# Schemat.net
KiCad netlist of a schematic drawn in EAGLE
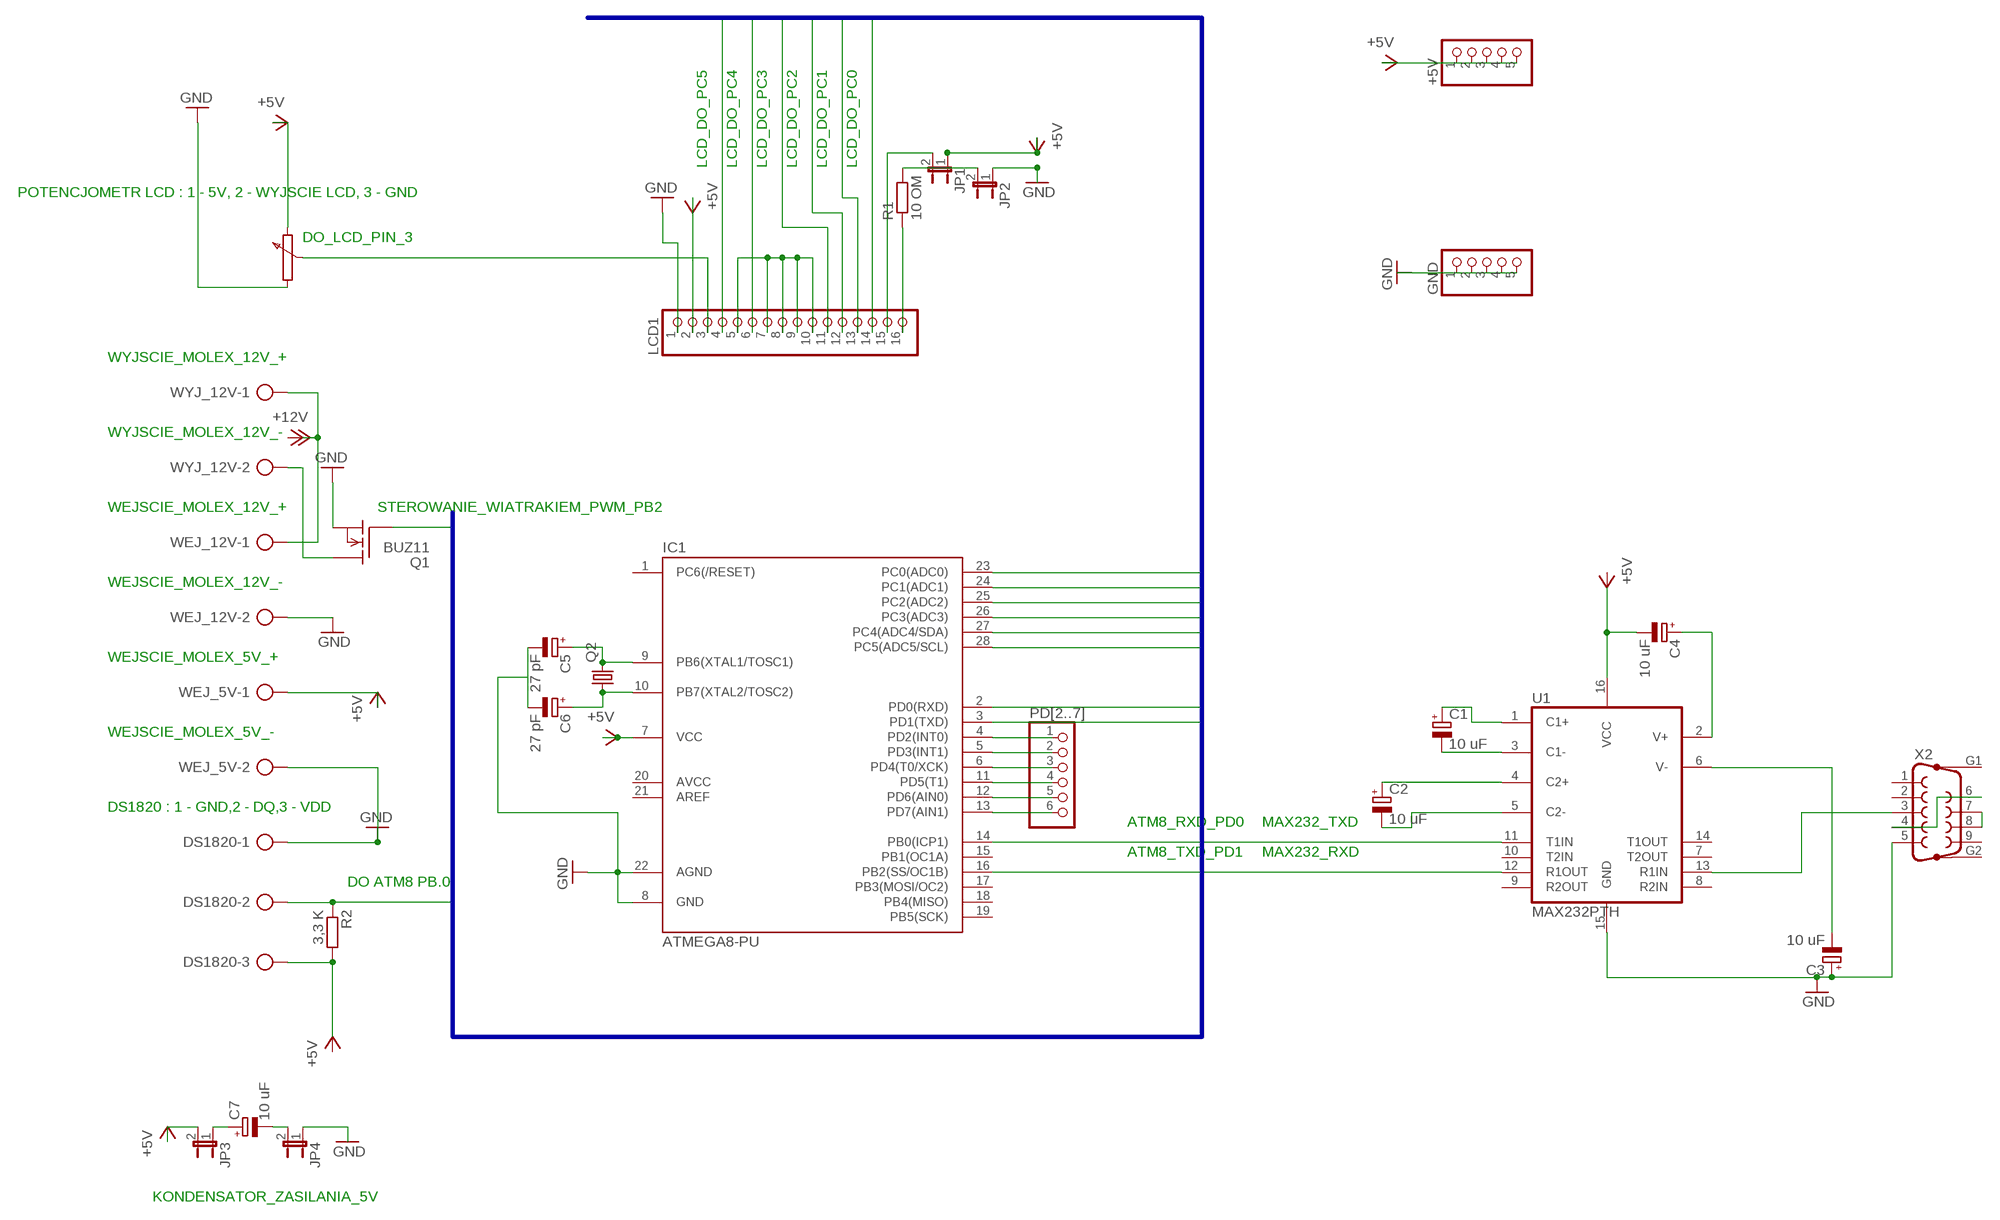
[diagram p0: schematic, sheet 1]

(export (version "E")
  (design (tool "Eeschema 10.0.6"))
  (components
    (comp (ref "+5V")
      (value "PINHD-1X5")
      (footprint "eagle-import:1X05")
      (libsource (lib "eagle-import") (part "PINHD-1X5"))
    )
    (comp (ref "C1")
      (value "10 uF")
      (footprint "eagle-import:E5-10,5")
      (libsource (lib "eagle-import") (part "CPOL-EUE5-10.5"))
    )
    (comp (ref "C2")
      (value "10 uF")
      (footprint "eagle-import:E5-10,5")
      (libsource (lib "eagle-import") (part "CPOL-EUE5-10.5"))
    )
    (comp (ref "C3")
      (value "10 uF")
      (footprint "eagle-import:E5-10,5")
      (libsource (lib "eagle-import") (part "CPOL-EUE5-10.5"))
    )
    (comp (ref "C4")
      (value "10 uF")
      (footprint "eagle-import:E5-10,5")
      (libsource (lib "eagle-import") (part "CPOL-EUE5-10.5"))
    )
    (comp (ref "C5")
      (value "27 pF")
      (footprint "eagle-import:E5-10,5")
      (libsource (lib "eagle-import") (part "CPOL-EUE5-10.5"))
    )
    (comp (ref "C6")
      (value "27 pF")
      (footprint "eagle-import:E5-10,5")
      (libsource (lib "eagle-import") (part "CPOL-EUE5-10.5"))
    )
    (comp (ref "C7")
      (value "10 uF")
      (footprint "eagle-import:E5-10,5")
      (libsource (lib "eagle-import") (part "CPOL-EUE5-10.5"))
    )
    (comp (ref "DS1820")
      (value "AK500/3-H")
      (footprint "eagle-import:AK500_3-H")
      (libsource (lib "eagle-import") (part "AK500/3-H"))
    )
    (comp (ref "GND")
      (value "PINHD-1X5")
      (footprint "eagle-import:1X05")
      (libsource (lib "eagle-import") (part "PINHD-1X5"))
    )
    (comp (ref "IC1")
      (value "ATMEGA8-PU")
      (footprint "eagle-import:DIL28-3")
      (libsource (lib "eagle-import") (part "ATMEGA8-PU"))
    )
    (comp (ref "JP1")
      (value "JP1E")
      (footprint "eagle-import:JP1")
      (libsource (lib "eagle-import") (part "JP1E"))
    )
    (comp (ref "JP2")
      (value "JP1E")
      (footprint "eagle-import:JP1")
      (libsource (lib "eagle-import") (part "JP1E"))
    )
    (comp (ref "JP3")
      (value "JP1E")
      (footprint "eagle-import:JP1")
      (libsource (lib "eagle-import") (part "JP1E"))
    )
    (comp (ref "JP4")
      (value "JP1E")
      (footprint "eagle-import:JP1")
      (libsource (lib "eagle-import") (part "JP1E"))
    )
    (comp (ref "LCD1")
      (value "PINHD-1X16")
      (footprint "eagle-import:1X16")
      (libsource (lib "eagle-import") (part "PINHD-1X16"))
    )
    (comp (ref "PD[2..7]")
      (value "PINHD-1X6")
      (footprint "eagle-import:1X06")
      (libsource (lib "eagle-import") (part "PINHD-1X6"))
    )
    (comp (ref "Q1")
      (value "BUZ11")
      (footprint "eagle-import:TO220")
      (libsource (lib "eagle-import") (part "BUZ11"))
    )
    (comp (ref "Q2")
      (value "CRYSTALHC49S")
      (footprint "eagle-import:HC49_S")
      (libsource (lib "eagle-import") (part "CRYSTALHC49S"))
    )
    (comp (ref "R1")
      (value "10 OM")
      (footprint "eagle-import:0207_15")
      (libsource (lib "eagle-import") (part "R-EU_0207/15"))
    )
    (comp (ref "R2")
      (value "3,3 K")
      (footprint "eagle-import:0207_15")
      (libsource (lib "eagle-import") (part "R-EU_0207/15"))
    )
    (comp (ref "U1")
      (value "MAX232PTH")
      (footprint "eagle-import:DIL16")
      (libsource (lib "eagle-import") (part "MAX232PTH"))
    )
    (comp (ref "WEJ_5V")
      (value "AK500/2-H")
      (footprint "eagle-import:AK500_2-H")
      (libsource (lib "eagle-import") (part "AK500/2-H"))
    )
    (comp (ref "WEJ_12V")
      (value "AK500/2-H")
      (footprint "eagle-import:AK500_2-H")
      (libsource (lib "eagle-import") (part "AK500/2-H"))
    )
    (comp (ref "WYJ_12V")
      (value "AK500/2-H")
      (footprint "eagle-import:AK500_2-H")
      (libsource (lib "eagle-import") (part "AK500/2-H"))
    )
    (comp (ref "X2")
      (value "F09HP")
      (footprint "eagle-import:F09HP")
      (libsource (lib "eagle-import") (part "F09HP"))
    )
  )
  (nets
    (net (code "1") (name "+5V") (class "Default")
      (node (ref "+5V") (pin "1") (pinfunction "1_1") (pintype "passive"))
      (node (ref "+5V") (pin "2") (pinfunction "2_2") (pintype "passive"))
      (node (ref "+5V") (pin "3") (pinfunction "3_3") (pintype "passive"))
      (node (ref "+5V") (pin "4") (pinfunction "4_4") (pintype "passive"))
      (node (ref "+5V") (pin "5") (pinfunction "5_5") (pintype "passive"))
      (node (ref "IC1") (pin "7") (pinfunction "VCC_7") (pintype "power_in"))
      (node (ref "JP1") (pin "1") (pinfunction "1_1") (pintype "passive"))
      (node (ref "JP3") (pin "2") (pinfunction "2_2") (pintype "passive"))
      (node (ref "LCD1") (pin "2") (pinfunction "2_2") (pintype "passive"))
      (node (ref "WEJ_5V") (pin "1") (pinfunction "KL_1") (pintype "passive"))
    )
    (net (code "3") (name "/PB0") (class "Default")
      (node (ref "DS1820") (pin "2") (pinfunction "KL_2") (pintype "passive"))
      (node (ref "IC1") (pin "14") (pinfunction "PB0(ICP1)_14") (pintype "bidirectional"))
      (node (ref "R2") (pin "1") (pinfunction "1_1") (pintype "passive"))
    )
    (net (code "4") (name "/PB2") (class "Default")
      (node (ref "IC1") (pin "16") (pinfunction "PB2(SS/OC1B)_16") (pintype "bidirectional"))
      (node (ref "Q1") (pin "1") (pinfunction "G_1") (pintype "passive"))
    )
    (net (code "5") (name "/PC0") (class "Default")
      (node (ref "IC1") (pin "23") (pinfunction "PC0(ADC0)_23") (pintype "bidirectional"))
      (node (ref "LCD1") (pin "14") (pinfunction "14_14") (pintype "passive"))
    )
    (net (code "6") (name "/PC1") (class "Default")
      (node (ref "IC1") (pin "24") (pinfunction "PC1(ADC1)_24") (pintype "bidirectional"))
      (node (ref "LCD1") (pin "13") (pinfunction "13_13") (pintype "passive"))
    )
    (net (code "7") (name "/PC2") (class "Default")
      (node (ref "IC1") (pin "25") (pinfunction "PC2(ADC2)_25") (pintype "bidirectional"))
      (node (ref "LCD1") (pin "12") (pinfunction "12_12") (pintype "passive"))
    )
    (net (code "8") (name "/PC3") (class "Default")
      (node (ref "IC1") (pin "26") (pinfunction "PC3(ADC3)_26") (pintype "bidirectional"))
      (node (ref "LCD1") (pin "11") (pinfunction "11_11") (pintype "passive"))
    )
    (net (code "9") (name "/PC4") (class "Default")
      (node (ref "IC1") (pin "27") (pinfunction "PC4(ADC4/SDA)_27") (pintype "bidirectional"))
      (node (ref "LCD1") (pin "6") (pinfunction "6_6") (pintype "passive"))
    )
    (net (code "10") (name "/PC5") (class "Default")
      (node (ref "IC1") (pin "28") (pinfunction "PC5(ADC5/SCL)_28") (pintype "bidirectional"))
      (node (ref "LCD1") (pin "4") (pinfunction "4_4") (pintype "passive"))
    )
    (net (code "11") (name "/PD0") (class "Default")
      (node (ref "IC1") (pin "2") (pinfunction "PD0(RXD)_2") (pintype "bidirectional"))
      (node (ref "U1") (pin "11") (pinfunction "T1IN_11") (pintype "input"))
    )
    (net (code "12") (name "/PD1") (class "Default")
      (node (ref "IC1") (pin "3") (pinfunction "PD1(TXD)_3") (pintype "bidirectional"))
      (node (ref "U1") (pin "12") (pinfunction "R1OUT_12") (pintype "output"))
    )
    (net (code "13") (name "GND") (class "Default")
      (node (ref "C3") (pin "+") (pinfunction "+_+") (pintype "passive"))
      (node (ref "C5") (pin "-") (pinfunction "-_-") (pintype "passive"))
      (node (ref "C6") (pin "-") (pinfunction "-_-") (pintype "passive"))
      (node (ref "DS1820") (pin "1") (pinfunction "KL_1") (pintype "passive"))
      (node (ref "GND") (pin "1") (pinfunction "1_1") (pintype "passive"))
      (node (ref "GND") (pin "2") (pinfunction "2_2") (pintype "passive"))
      (node (ref "GND") (pin "3") (pinfunction "3_3") (pintype "passive"))
      (node (ref "GND") (pin "4") (pinfunction "4_4") (pintype "passive"))
      (node (ref "GND") (pin "5") (pinfunction "5_5") (pintype "passive"))
      (node (ref "IC1") (pin "22") (pinfunction "AGND_22") (pintype "power_in"))
      (node (ref "IC1") (pin "8") (pinfunction "GND_8") (pintype "power_in"))
      (node (ref "JP2") (pin "1") (pinfunction "1_1") (pintype "passive"))
      (node (ref "JP4") (pin "1") (pinfunction "1_1") (pintype "passive"))
      (node (ref "LCD1") (pin "1") (pinfunction "1_1") (pintype "passive"))
      (node (ref "Q1") (pin "3") (pinfunction "S_3") (pintype "passive"))
      (node (ref "U1") (pin "15") (pinfunction "GND_15") (pintype "bidirectional"))
      (node (ref "WEJ_12V") (pin "2") (pinfunction "KL_2") (pintype "passive"))
      (node (ref "WEJ_5V") (pin "2") (pinfunction "KL_2") (pintype "passive"))
      (node (ref "X2") (pin "5") (pinfunction "5_5") (pintype "passive"))
    )
    (net (code "14") (name "Net-(C7-Pad+)") (class "Default")
      (node (ref "C7") (pin "+") (pinfunction "+_+") (pintype "passive"))
      (node (ref "JP3") (pin "1") (pinfunction "1_1") (pintype "passive"))
    )
    (net (code "15") (name "Net-(C7-Pad-)") (class "Default")
      (node (ref "C7") (pin "-") (pinfunction "-_-") (pintype "passive"))
      (node (ref "JP4") (pin "2") (pinfunction "2_2") (pintype "passive"))
    )
    (net (code "16") (name "Net-(DS1820C-KL)") (class "Default")
      (node (ref "DS1820") (pin "3") (pinfunction "KL_3") (pintype "passive"))
      (node (ref "R2") (pin "2") (pinfunction "2_2") (pintype "passive"))
    )
    (net (code "17") (name "Net-(IC1-PB6(XTAL1{slash}TOSC1))") (class "Default")
      (node (ref "C5") (pin "+") (pinfunction "+_+") (pintype "passive"))
      (node (ref "IC1") (pin "9") (pinfunction "PB6(XTAL1/TOSC1)_9") (pintype "bidirectional"))
      (node (ref "Q2") (pin "2") (pinfunction "2_2") (pintype "passive"))
    )
    (net (code "18") (name "Net-(IC1-PB7(XTAL2{slash}TOSC2))") (class "Default")
      (node (ref "C6") (pin "+") (pinfunction "+_+") (pintype "passive"))
      (node (ref "IC1") (pin "10") (pinfunction "PB7(XTAL2/TOSC2)_10") (pintype "bidirectional"))
      (node (ref "Q2") (pin "1") (pinfunction "1_1") (pintype "passive"))
    )
    (net (code "19") (name "Net-(IC1-PD2(INT0))") (class "Default")
      (node (ref "IC1") (pin "4") (pinfunction "PD2(INT0)_4") (pintype "bidirectional"))
      (node (ref "PD[2..7]") (pin "1") (pinfunction "1_1") (pintype "passive"))
    )
    (net (code "20") (name "Net-(IC1-PD3(INT1))") (class "Default")
      (node (ref "IC1") (pin "5") (pinfunction "PD3(INT1)_5") (pintype "bidirectional"))
      (node (ref "PD[2..7]") (pin "2") (pinfunction "2_2") (pintype "passive"))
    )
    (net (code "21") (name "Net-(IC1-PD4(T0{slash}XCK))") (class "Default")
      (node (ref "IC1") (pin "6") (pinfunction "PD4(T0/XCK)_6") (pintype "bidirectional"))
      (node (ref "PD[2..7]") (pin "3") (pinfunction "3_3") (pintype "passive"))
    )
    (net (code "22") (name "Net-(IC1-PD5(T1))") (class "Default")
      (node (ref "IC1") (pin "11") (pinfunction "PD5(T1)_11") (pintype "bidirectional"))
      (node (ref "PD[2..7]") (pin "4") (pinfunction "4_4") (pintype "passive"))
    )
    (net (code "23") (name "Net-(IC1-PD6(AIN0))") (class "Default")
      (node (ref "IC1") (pin "12") (pinfunction "PD6(AIN0)_12") (pintype "bidirectional"))
      (node (ref "PD[2..7]") (pin "5") (pinfunction "5_5") (pintype "passive"))
    )
    (net (code "24") (name "Net-(IC1-PD7(AIN1))") (class "Default")
      (node (ref "IC1") (pin "13") (pinfunction "PD7(AIN1)_13") (pintype "bidirectional"))
      (node (ref "PD[2..7]") (pin "6") (pinfunction "6_6") (pintype "passive"))
    )
    (net (code "25") (name "Net-(JP1-Pad2)") (class "Default")
      (node (ref "JP1") (pin "2") (pinfunction "2_2") (pintype "passive"))
      (node (ref "LCD1") (pin "15") (pinfunction "15_15") (pintype "passive"))
    )
    (net (code "26") (name "Net-(JP2-Pad2)") (class "Default")
      (node (ref "JP2") (pin "2") (pinfunction "2_2") (pintype "passive"))
      (node (ref "R1") (pin "2") (pinfunction "2_2") (pintype "passive"))
    )
    (net (code "27") (name "Net-(LCD1-Pad10)") (class "Default")
      (node (ref "LCD1") (pin "10") (pinfunction "10_10") (pintype "passive"))
      (node (ref "LCD1") (pin "5") (pinfunction "5_5") (pintype "passive"))
      (node (ref "LCD1") (pin "7") (pinfunction "7_7") (pintype "passive"))
      (node (ref "LCD1") (pin "8") (pinfunction "8_8") (pintype "passive"))
      (node (ref "LCD1") (pin "9") (pinfunction "9_9") (pintype "passive"))
    )
    (net (code "28") (name "Net-(LCD1-Pad16)") (class "Default")
      (node (ref "LCD1") (pin "16") (pinfunction "16_16") (pintype "passive"))
      (node (ref "R1") (pin "1") (pinfunction "1_1") (pintype "passive"))
    )
    (net (code "29") (name "Net-(Q1-D)") (class "Default")
      (node (ref "Q1") (pin "2") (pinfunction "D_2") (pintype "passive"))
      (node (ref "WYJ_12V") (pin "2") (pinfunction "KL_2") (pintype "passive"))
    )
    (net (code "30") (name "Net-(U1-C1+)") (class "Default")
      (node (ref "C1") (pin "+") (pinfunction "+_+") (pintype "passive"))
      (node (ref "U1") (pin "1") (pinfunction "C1+_1") (pintype "bidirectional"))
    )
    (net (code "31") (name "Net-(U1-C1-)") (class "Default")
      (node (ref "C1") (pin "-") (pinfunction "-_-") (pintype "passive"))
      (node (ref "U1") (pin "3") (pinfunction "C1-_3") (pintype "bidirectional"))
    )
    (net (code "32") (name "Net-(U1-C2+)") (class "Default")
      (node (ref "C2") (pin "+") (pinfunction "+_+") (pintype "passive"))
      (node (ref "U1") (pin "4") (pinfunction "C2+_4") (pintype "bidirectional"))
    )
    (net (code "33") (name "Net-(U1-C2-)") (class "Default")
      (node (ref "C2") (pin "-") (pinfunction "-_-") (pintype "passive"))
      (node (ref "U1") (pin "5") (pinfunction "C2-_5") (pintype "bidirectional"))
    )
    (net (code "34") (name "Net-(U1-R1IN)") (class "Default")
      (node (ref "U1") (pin "13") (pinfunction "R1IN_13") (pintype "input"))
      (node (ref "X2") (pin "3") (pinfunction "3_3") (pintype "passive"))
    )
    (net (code "35") (name "Net-(U1-V+)") (class "Default")
      (node (ref "C4") (pin "+") (pinfunction "+_+") (pintype "passive"))
      (node (ref "U1") (pin "2") (pinfunction "V+_2") (pintype "bidirectional"))
    )
    (net (code "36") (name "Net-(U1-V-)") (class "Default")
      (node (ref "C3") (pin "-") (pinfunction "-_-") (pintype "passive"))
      (node (ref "U1") (pin "6") (pinfunction "V-_6") (pintype "bidirectional"))
    )
    (net (code "37") (name "Net-(U1-VCC)") (class "Default")
      (node (ref "C4") (pin "-") (pinfunction "-_-") (pintype "passive"))
      (node (ref "U1") (pin "16") (pinfunction "VCC_16") (pintype "bidirectional"))
    )
    (net (code "38") (name "Net-(WEJ_12VA-KL)") (class "Default")
      (node (ref "WEJ_12V") (pin "1") (pinfunction "KL_1") (pintype "passive"))
      (node (ref "WYJ_12V") (pin "1") (pinfunction "KL_1") (pintype "passive"))
    )
    (net (code "39") (name "Net-(X2-Pad4)") (class "Default")
      (node (ref "X2") (pin "4") (pinfunction "4_4") (pintype "passive"))
      (node (ref "X2") (pin "6") (pinfunction "6_6") (pintype "passive"))
    )
    (net (code "40") (name "Net-(X2-Pad7)") (class "Default")
      (node (ref "X2") (pin "7") (pinfunction "7_7") (pintype "passive"))
      (node (ref "X2") (pin "8") (pinfunction "8_8") (pintype "passive"))
    )
    (net (code "41") (name "unconnected-(IC1-AREF-Pad21)") (class "Default")
      (node (ref "IC1") (pin "21") (pinfunction "AREF_21") (pintype "passive"))
    )
    (net (code "42") (name "unconnected-(IC1-AVCC-Pad20)") (class "Default")
      (node (ref "IC1") (pin "20") (pinfunction "AVCC_20") (pintype "passive"))
    )
    (net (code "43") (name "unconnected-(IC1-PB1(OC1A)-Pad15)") (class "Default")
      (node (ref "IC1") (pin "15") (pinfunction "PB1(OC1A)_15") (pintype "bidirectional"))
    )
    (net (code "44") (name "unconnected-(IC1-PB3(MOSI{slash}OC2)-Pad17)") (class "Default")
      (node (ref "IC1") (pin "17") (pinfunction "PB3(MOSI/OC2)_17") (pintype "bidirectional"))
    )
    (net (code "45") (name "unconnected-(IC1-PB4(MISO)-Pad18)") (class "Default")
      (node (ref "IC1") (pin "18") (pinfunction "PB4(MISO)_18") (pintype "bidirectional"))
    )
    (net (code "46") (name "unconnected-(IC1-PB5(SCK)-Pad19)") (class "Default")
      (node (ref "IC1") (pin "19") (pinfunction "PB5(SCK)_19") (pintype "bidirectional"))
    )
    (net (code "47") (name "unconnected-(IC1-PC6({slash}RESET)-Pad1)") (class "Default")
      (node (ref "IC1") (pin "1") (pinfunction "PC6(/RESET)_1") (pintype "bidirectional"))
    )
    (net (code "48") (name "unconnected-(LCD1-Pad3)") (class "Default")
      (node (ref "LCD1") (pin "3") (pinfunction "3_3") (pintype "passive"))
    )
    (net (code "49") (name "unconnected-(U1-R2IN-Pad8)") (class "Default")
      (node (ref "U1") (pin "8") (pinfunction "R2IN_8") (pintype "input"))
    )
    (net (code "50") (name "unconnected-(U1-R2OUT-Pad9)") (class "Default")
      (node (ref "U1") (pin "9") (pinfunction "R2OUT_9") (pintype "output"))
    )
    (net (code "51") (name "unconnected-(U1-T1OUT-Pad14)") (class "Default")
      (node (ref "U1") (pin "14") (pinfunction "T1OUT_14") (pintype "output"))
    )
    (net (code "52") (name "unconnected-(U1-T2IN-Pad10)") (class "Default")
      (node (ref "U1") (pin "10") (pinfunction "T2IN_10") (pintype "input"))
    )
    (net (code "53") (name "unconnected-(U1-T2OUT-Pad7)") (class "Default")
      (node (ref "U1") (pin "7") (pinfunction "T2OUT_7") (pintype "output"))
    )
    (net (code "54") (name "unconnected-(X2-Pad1)") (class "Default")
      (node (ref "X2") (pin "1") (pinfunction "1_1") (pintype "passive"))
    )
    (net (code "55") (name "unconnected-(X2-Pad2)") (class "Default")
      (node (ref "X2") (pin "2") (pinfunction "2_2") (pintype "passive"))
    )
    (net (code "56") (name "unconnected-(X2-Pad9)") (class "Default")
      (node (ref "X2") (pin "9") (pinfunction "9_9") (pintype "passive"))
    )
    (net (code "57") (name "unconnected-(X2-PadG1)") (class "Default")
      (node (ref "X2") (pin "G1") (pinfunction "G1_G1") (pintype "passive"))
    )
    (net (code "58") (name "unconnected-(X2-PadG2)") (class "Default")
      (node (ref "X2") (pin "G2") (pinfunction "G2_G2") (pintype "passive"))
    )
  )
)
